# OLED.net
KiCad netlist of a schematic drawn in EAGLE
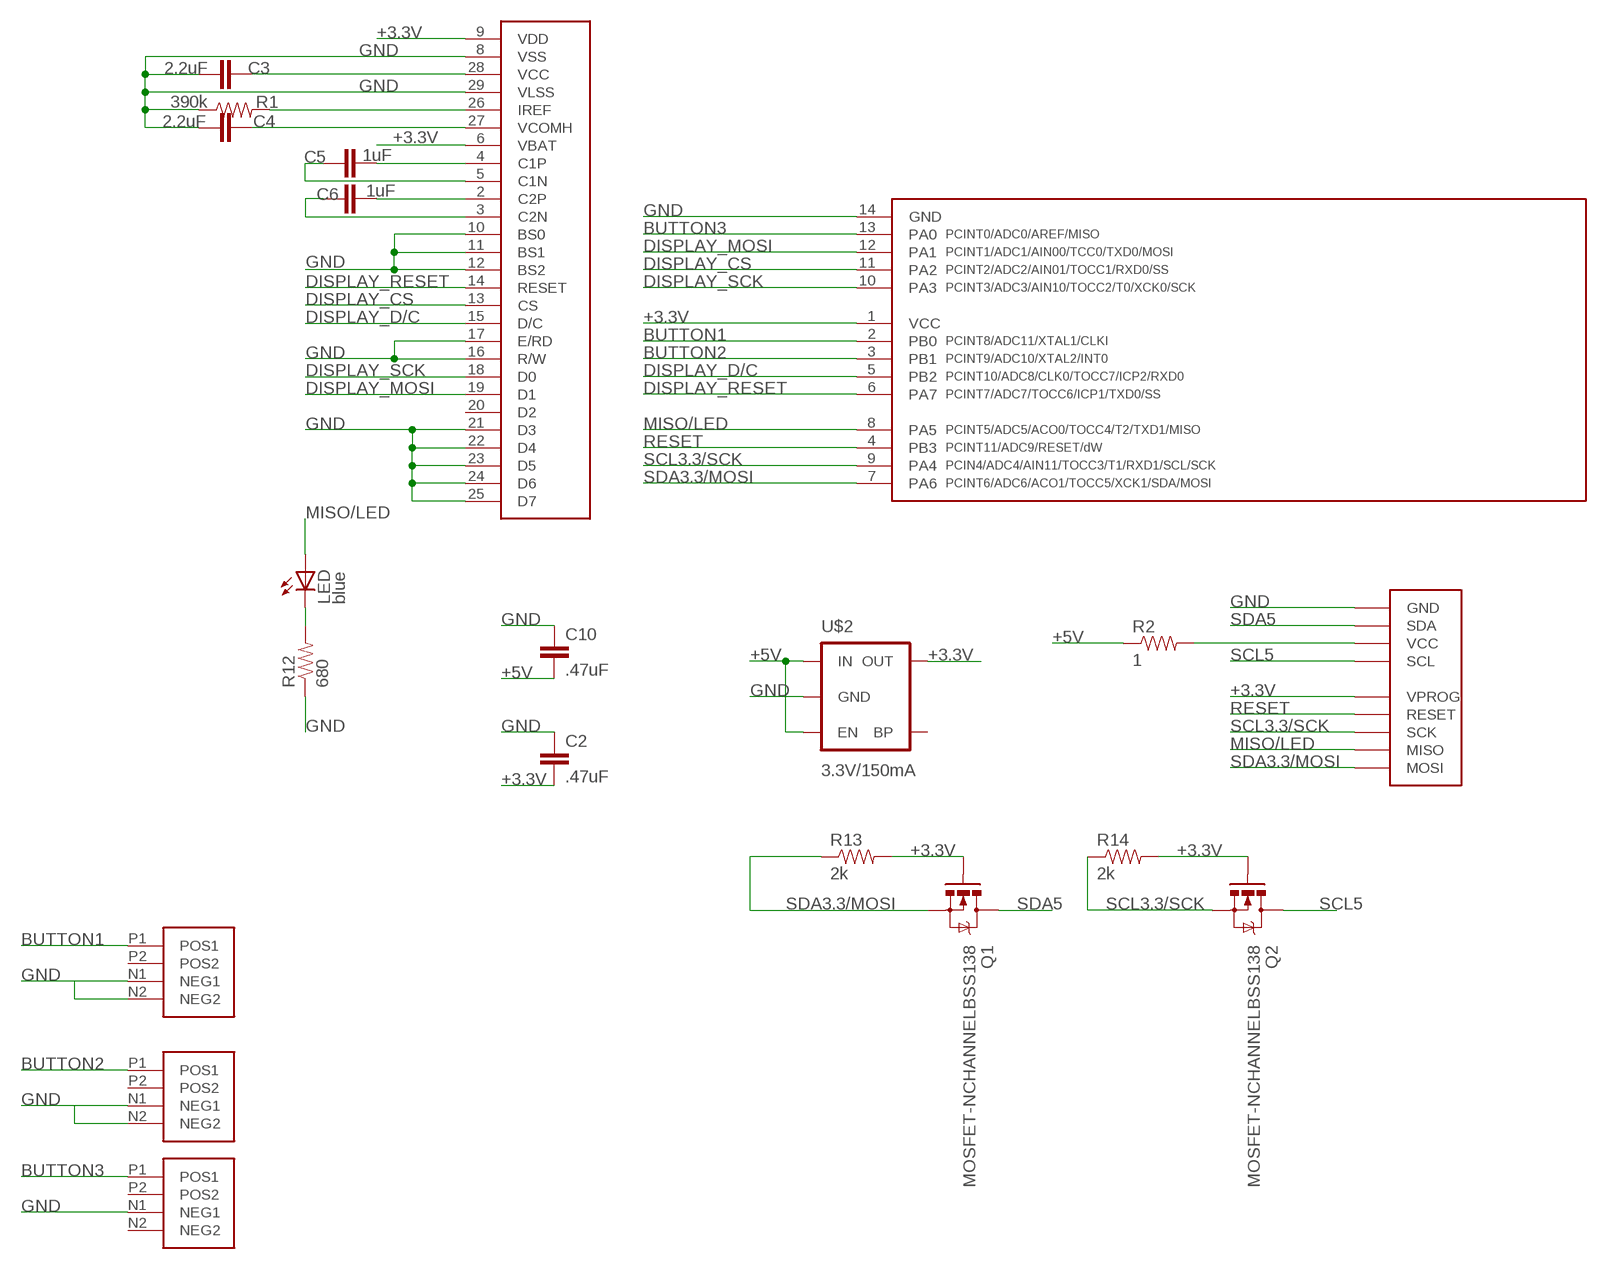
[diagram p0: schematic, sheet 1]

(export (version "E")
  (design (tool "Eeschema 10.0.6"))
  (components
    (comp (ref "C2")
      (value ".47uF")
      (footprint "eagle-import:0805")
      (libsource (lib "eagle-import") (part "CAP0805"))
    )
    (comp (ref "C3")
      (value "2.2uF")
      (footprint "eagle-import:0805")
      (libsource (lib "eagle-import") (part "CAP0805"))
    )
    (comp (ref "C4")
      (value "2.2uF")
      (footprint "eagle-import:0805")
      (libsource (lib "eagle-import") (part "CAP0805"))
    )
    (comp (ref "C5")
      (value "1uF")
      (footprint "eagle-import:0805")
      (libsource (lib "eagle-import") (part "CAP0805"))
    )
    (comp (ref "C6")
      (value "1uF")
      (footprint "eagle-import:0805")
      (libsource (lib "eagle-import") (part "CAP0805"))
    )
    (comp (ref "C10")
      (value ".47uF")
      (footprint "eagle-import:0805")
      (libsource (lib "eagle-import") (part "CAP0805"))
    )
    (comp (ref "LED")
      (value "blue")
      (footprint "eagle-import:CHIPLED_1206")
      (libsource (lib "eagle-import") (part "LEDCHIPLED_1206"))
    )
    (comp (ref "Q1")
      (value "MOSFET-NCHANNELBSS138")
      (footprint "eagle-import:SOT23")
      (libsource (lib "eagle-import") (part "MOSFET-NCHANNELBSS138"))
    )
    (comp (ref "Q2")
      (value "MOSFET-NCHANNELBSS138")
      (footprint "eagle-import:SOT23")
      (libsource (lib "eagle-import") (part "MOSFET-NCHANNELBSS138"))
    )
    (comp (ref "R1")
      (value "390k")
      (footprint "eagle-import:0603-RES")
      (libsource (lib "eagle-import") (part "RESISTOR0603"))
    )
    (comp (ref "R2")
      (value "1")
      (footprint "eagle-import:0805")
      (libsource (lib "eagle-import") (part "RESISTOR0805-RES"))
    )
    (comp (ref "R12")
      (value "680")
      (footprint "eagle-import:0805")
      (libsource (lib "eagle-import") (part "RESISTOR0805-RES"))
    )
    (comp (ref "R13")
      (value "2k")
      (footprint "eagle-import:0805")
      (libsource (lib "eagle-import") (part "RESISTOR0805-RES"))
    )
    (comp (ref "R14")
      (value "2k")
      (footprint "eagle-import:0805")
      (libsource (lib "eagle-import") (part "RESISTOR0805-RES"))
    )
    (comp (ref "U$1")
      (value "OLEDREVERSE")
      (footprint "eagle-import:FPC-30-REVERSE")
      (libsource (lib "eagle-import") (part "OLEDREVERSE"))
    )
    (comp (ref "U$2")
      (value "3.3V/150mA")
      (footprint "eagle-import:SOT23-5")
      (libsource (lib "eagle-import") (part "V_REG_MIC52053.3V"))
    )
    (comp (ref "U$3")
      (value "TINY841")
      (footprint "eagle-import:SOIC14")
      (libsource (lib "eagle-import") (part "TINY841"))
    )
    (comp (ref "U$4")
      (value "FOOTPRINTFOOTPRINT-2")
      (footprint "eagle-import:FOOTPRINT2")
      (libsource (lib "eagle-import") (part "FOOTPRINTFOOTPRINT-2"))
    )
    (comp (ref "U$5")
      (value "TACT-SWITCHKMR2")
      (footprint "eagle-import:TACT-SWITCH-SMALL")
      (libsource (lib "eagle-import") (part "TACT-SWITCHKMR2"))
    )
    (comp (ref "U$6")
      (value "TACT-SWITCHKMR2")
      (footprint "eagle-import:TACT-SWITCH-SMALL")
      (libsource (lib "eagle-import") (part "TACT-SWITCHKMR2"))
    )
    (comp (ref "U$7")
      (value "TACT-SWITCHKMR2")
      (footprint "eagle-import:TACT-SWITCH-SMALL")
      (libsource (lib "eagle-import") (part "TACT-SWITCHKMR2"))
    )
  )
  (nets
    (net (code "1") (name "/+3.3V") (class "Default")
      (node (ref "C2") (pin "2") (pinfunction "2_2") (pintype "passive"))
      (node (ref "Q1") (pin "1") (pinfunction "G_1") (pintype "passive"))
      (node (ref "Q2") (pin "1") (pinfunction "G_1") (pintype "passive"))
      (node (ref "R13") (pin "2") (pinfunction "2_2") (pintype "passive"))
      (node (ref "R14") (pin "2") (pinfunction "2_2") (pintype "passive"))
      (node (ref "U$1") (pin "6") (pinfunction "VBAT_6") (pintype "bidirectional"))
      (node (ref "U$1") (pin "9") (pinfunction "VDD_9") (pintype "bidirectional"))
      (node (ref "U$2") (pin "5") (pinfunction "OUT_5") (pintype "passive"))
      (node (ref "U$3") (pin "1") (pinfunction "VCC_1") (pintype "bidirectional"))
      (node (ref "U$4") (pin "PROG0") (pinfunction "VPROG_PROG0") (pintype "bidirectional"))
    )
    (net (code "2") (name "/+5V") (class "Default")
      (node (ref "C10") (pin "2") (pinfunction "2_2") (pintype "passive"))
      (node (ref "R2") (pin "1") (pinfunction "1_1") (pintype "passive"))
      (node (ref "U$2") (pin "1") (pinfunction "IN_1") (pintype "input"))
      (node (ref "U$2") (pin "3") (pinfunction "EN_3") (pintype "input"))
    )
    (net (code "3") (name "/BUTTON1") (class "Default")
      (node (ref "U$3") (pin "2") (pinfunction "PB0_2") (pintype "bidirectional"))
      (node (ref "U$5") (pin "P1") (pinfunction "POS1_P1") (pintype "bidirectional"))
    )
    (net (code "4") (name "/BUTTON2") (class "Default")
      (node (ref "U$3") (pin "3") (pinfunction "PB1_3") (pintype "bidirectional"))
      (node (ref "U$6") (pin "P1") (pinfunction "POS1_P1") (pintype "bidirectional"))
    )
    (net (code "5") (name "/BUTTON3") (class "Default")
      (node (ref "U$3") (pin "13") (pinfunction "PA0_13") (pintype "bidirectional"))
      (node (ref "U$7") (pin "P1") (pinfunction "POS1_P1") (pintype "bidirectional"))
    )
    (net (code "6") (name "/DISPLAY_CS") (class "Default")
      (node (ref "U$1") (pin "13") (pinfunction "CS_13") (pintype "bidirectional"))
      (node (ref "U$3") (pin "11") (pinfunction "PA2_11") (pintype "bidirectional"))
    )
    (net (code "7") (name "/DISPLAY_D{slash}C") (class "Default")
      (node (ref "U$1") (pin "15") (pinfunction "D/C_15") (pintype "bidirectional"))
      (node (ref "U$3") (pin "5") (pinfunction "PB2_5") (pintype "bidirectional"))
    )
    (net (code "8") (name "/DISPLAY_MOSI") (class "Default")
      (node (ref "U$1") (pin "19") (pinfunction "D1_19") (pintype "bidirectional"))
      (node (ref "U$3") (pin "12") (pinfunction "PA1_12") (pintype "bidirectional"))
    )
    (net (code "9") (name "/DISPLAY_RESET") (class "Default")
      (node (ref "U$1") (pin "14") (pinfunction "RESET_14") (pintype "bidirectional"))
      (node (ref "U$3") (pin "6") (pinfunction "PA7_6") (pintype "bidirectional"))
    )
    (net (code "10") (name "/DISPLAY_SCK") (class "Default")
      (node (ref "U$1") (pin "18") (pinfunction "D0_18") (pintype "bidirectional"))
      (node (ref "U$3") (pin "10") (pinfunction "PA3_10") (pintype "bidirectional"))
    )
    (net (code "11") (name "/GND") (class "Default")
      (node (ref "C10") (pin "1") (pinfunction "1_1") (pintype "passive"))
      (node (ref "C2") (pin "1") (pinfunction "1_1") (pintype "passive"))
      (node (ref "C3") (pin "2") (pinfunction "2_2") (pintype "passive"))
      (node (ref "C4") (pin "2") (pinfunction "2_2") (pintype "passive"))
      (node (ref "R1") (pin "1") (pinfunction "1_1") (pintype "passive"))
      (node (ref "R12") (pin "1") (pinfunction "1_1") (pintype "passive"))
      (node (ref "U$1") (pin "10") (pinfunction "BS0_10") (pintype "bidirectional"))
      (node (ref "U$1") (pin "11") (pinfunction "BS1_11") (pintype "bidirectional"))
      (node (ref "U$1") (pin "12") (pinfunction "BS2_12") (pintype "bidirectional"))
      (node (ref "U$1") (pin "16") (pinfunction "R/W_16") (pintype "bidirectional"))
      (node (ref "U$1") (pin "17") (pinfunction "E/RD_17") (pintype "bidirectional"))
      (node (ref "U$1") (pin "21") (pinfunction "D3_21") (pintype "bidirectional"))
      (node (ref "U$1") (pin "22") (pinfunction "D4_22") (pintype "bidirectional"))
      (node (ref "U$1") (pin "23") (pinfunction "D5_23") (pintype "bidirectional"))
      (node (ref "U$1") (pin "24") (pinfunction "D6_24") (pintype "bidirectional"))
      (node (ref "U$1") (pin "25") (pinfunction "D7_25") (pintype "bidirectional"))
      (node (ref "U$1") (pin "29") (pinfunction "VLSS_29") (pintype "bidirectional"))
      (node (ref "U$1") (pin "8") (pinfunction "VSS_8") (pintype "bidirectional"))
      (node (ref "U$2") (pin "2") (pinfunction "GND_2") (pintype "input"))
      (node (ref "U$3") (pin "14") (pinfunction "GND_14") (pintype "bidirectional"))
      (node (ref "U$4") (pin "BUS0") (pinfunction "GND_BUS0") (pintype "bidirectional"))
      (node (ref "U$5") (pin "N1") (pinfunction "NEG1_N1") (pintype "bidirectional"))
      (node (ref "U$5") (pin "N2") (pinfunction "NEG2_N2") (pintype "bidirectional"))
      (node (ref "U$6") (pin "N1") (pinfunction "NEG1_N1") (pintype "bidirectional"))
      (node (ref "U$6") (pin "N2") (pinfunction "NEG2_N2") (pintype "bidirectional"))
      (node (ref "U$7") (pin "N1") (pinfunction "NEG1_N1") (pintype "bidirectional"))
    )
    (net (code "12") (name "/MISO{slash}LED") (class "Default")
      (node (ref "LED") (pin "A") (pinfunction "A_A") (pintype "passive"))
      (node (ref "U$3") (pin "8") (pinfunction "PA5_8") (pintype "bidirectional"))
      (node (ref "U$4") (pin "PROG3") (pinfunction "MISO_PROG3") (pintype "bidirectional"))
    )
    (net (code "13") (name "/RESET") (class "Default")
      (node (ref "U$3") (pin "4") (pinfunction "PB3_4") (pintype "bidirectional"))
      (node (ref "U$4") (pin "PROG1") (pinfunction "RESET_PROG1") (pintype "bidirectional"))
    )
    (net (code "14") (name "/SCL3.3{slash}SCK") (class "Default")
      (node (ref "Q2") (pin "2") (pinfunction "S_2") (pintype "passive"))
      (node (ref "R14") (pin "1") (pinfunction "1_1") (pintype "passive"))
      (node (ref "U$3") (pin "9") (pinfunction "PA4_9") (pintype "bidirectional"))
      (node (ref "U$4") (pin "PROG2") (pinfunction "SCK_PROG2") (pintype "bidirectional"))
    )
    (net (code "15") (name "/SCL5") (class "Default")
      (node (ref "Q2") (pin "3") (pinfunction "D_3") (pintype "passive"))
      (node (ref "U$4") (pin "BUS3") (pinfunction "SCL_BUS3") (pintype "bidirectional"))
    )
    (net (code "16") (name "/SDA3.3{slash}MOSI") (class "Default")
      (node (ref "Q1") (pin "2") (pinfunction "S_2") (pintype "passive"))
      (node (ref "R13") (pin "1") (pinfunction "1_1") (pintype "passive"))
      (node (ref "U$3") (pin "7") (pinfunction "PA6_7") (pintype "bidirectional"))
      (node (ref "U$4") (pin "PROG4") (pinfunction "MOSI_PROG4") (pintype "bidirectional"))
    )
    (net (code "17") (name "/SDA5") (class "Default")
      (node (ref "Q1") (pin "3") (pinfunction "D_3") (pintype "passive"))
      (node (ref "U$4") (pin "BUS1") (pinfunction "SDA_BUS1") (pintype "bidirectional"))
    )
    (net (code "18") (name "Net-(LED-PadC)") (class "Default")
      (node (ref "LED") (pin "C") (pinfunction "C_C") (pintype "passive"))
      (node (ref "R12") (pin "2") (pinfunction "2_2") (pintype "passive"))
    )
    (net (code "19") (name "Net-(U$1-C1N)") (class "Default")
      (node (ref "C5") (pin "1") (pinfunction "1_1") (pintype "passive"))
      (node (ref "U$1") (pin "5") (pinfunction "C1N_5") (pintype "bidirectional"))
    )
    (net (code "20") (name "Net-(U$1-C1P)") (class "Default")
      (node (ref "C5") (pin "2") (pinfunction "2_2") (pintype "passive"))
      (node (ref "U$1") (pin "4") (pinfunction "C1P_4") (pintype "bidirectional"))
    )
    (net (code "21") (name "Net-(U$1-C2N)") (class "Default")
      (node (ref "C6") (pin "1") (pinfunction "1_1") (pintype "passive"))
      (node (ref "U$1") (pin "3") (pinfunction "C2N_3") (pintype "bidirectional"))
    )
    (net (code "22") (name "Net-(U$1-C2P)") (class "Default")
      (node (ref "C6") (pin "2") (pinfunction "2_2") (pintype "passive"))
      (node (ref "U$1") (pin "2") (pinfunction "C2P_2") (pintype "bidirectional"))
    )
    (net (code "23") (name "Net-(U$1-IREF)") (class "Default")
      (node (ref "R1") (pin "2") (pinfunction "2_2") (pintype "passive"))
      (node (ref "U$1") (pin "26") (pinfunction "IREF_26") (pintype "bidirectional"))
    )
    (net (code "24") (name "Net-(U$1-VCC)") (class "Default")
      (node (ref "C3") (pin "1") (pinfunction "1_1") (pintype "passive"))
      (node (ref "U$1") (pin "28") (pinfunction "VCC_28") (pintype "bidirectional"))
    )
    (net (code "25") (name "Net-(U$1-VCOMH)") (class "Default")
      (node (ref "C4") (pin "1") (pinfunction "1_1") (pintype "passive"))
      (node (ref "U$1") (pin "27") (pinfunction "VCOMH_27") (pintype "bidirectional"))
    )
    (net (code "26") (name "Net-(U$4-VCC)") (class "Default")
      (node (ref "R2") (pin "2") (pinfunction "2_2") (pintype "passive"))
      (node (ref "U$4") (pin "BUS2") (pinfunction "VCC_BUS2") (pintype "bidirectional"))
    )
    (net (code "27") (name "unconnected-(U$1-D2-Pad20)") (class "Default")
      (node (ref "U$1") (pin "20") (pinfunction "D2_20") (pintype "bidirectional"))
    )
    (net (code "28") (name "unconnected-(U$2-BP-Pad4)") (class "Default")
      (node (ref "U$2") (pin "4") (pinfunction "BP_4") (pintype "input"))
    )
    (net (code "29") (name "unconnected-(U$5-POS2-PadP2)") (class "Default")
      (node (ref "U$5") (pin "P2") (pinfunction "POS2_P2") (pintype "bidirectional"))
    )
    (net (code "30") (name "unconnected-(U$6-POS2-PadP2)") (class "Default")
      (node (ref "U$6") (pin "P2") (pinfunction "POS2_P2") (pintype "bidirectional"))
    )
    (net (code "31") (name "unconnected-(U$7-NEG2-PadN2)") (class "Default")
      (node (ref "U$7") (pin "N2") (pinfunction "NEG2_N2") (pintype "bidirectional"))
    )
    (net (code "32") (name "unconnected-(U$7-POS2-PadP2)") (class "Default")
      (node (ref "U$7") (pin "P2") (pinfunction "POS2_P2") (pintype "bidirectional"))
    )
  )
)
